# IO_Shield_With_Power_Supply_PCB.net
KiCad netlist of a schematic drawn in EAGLE
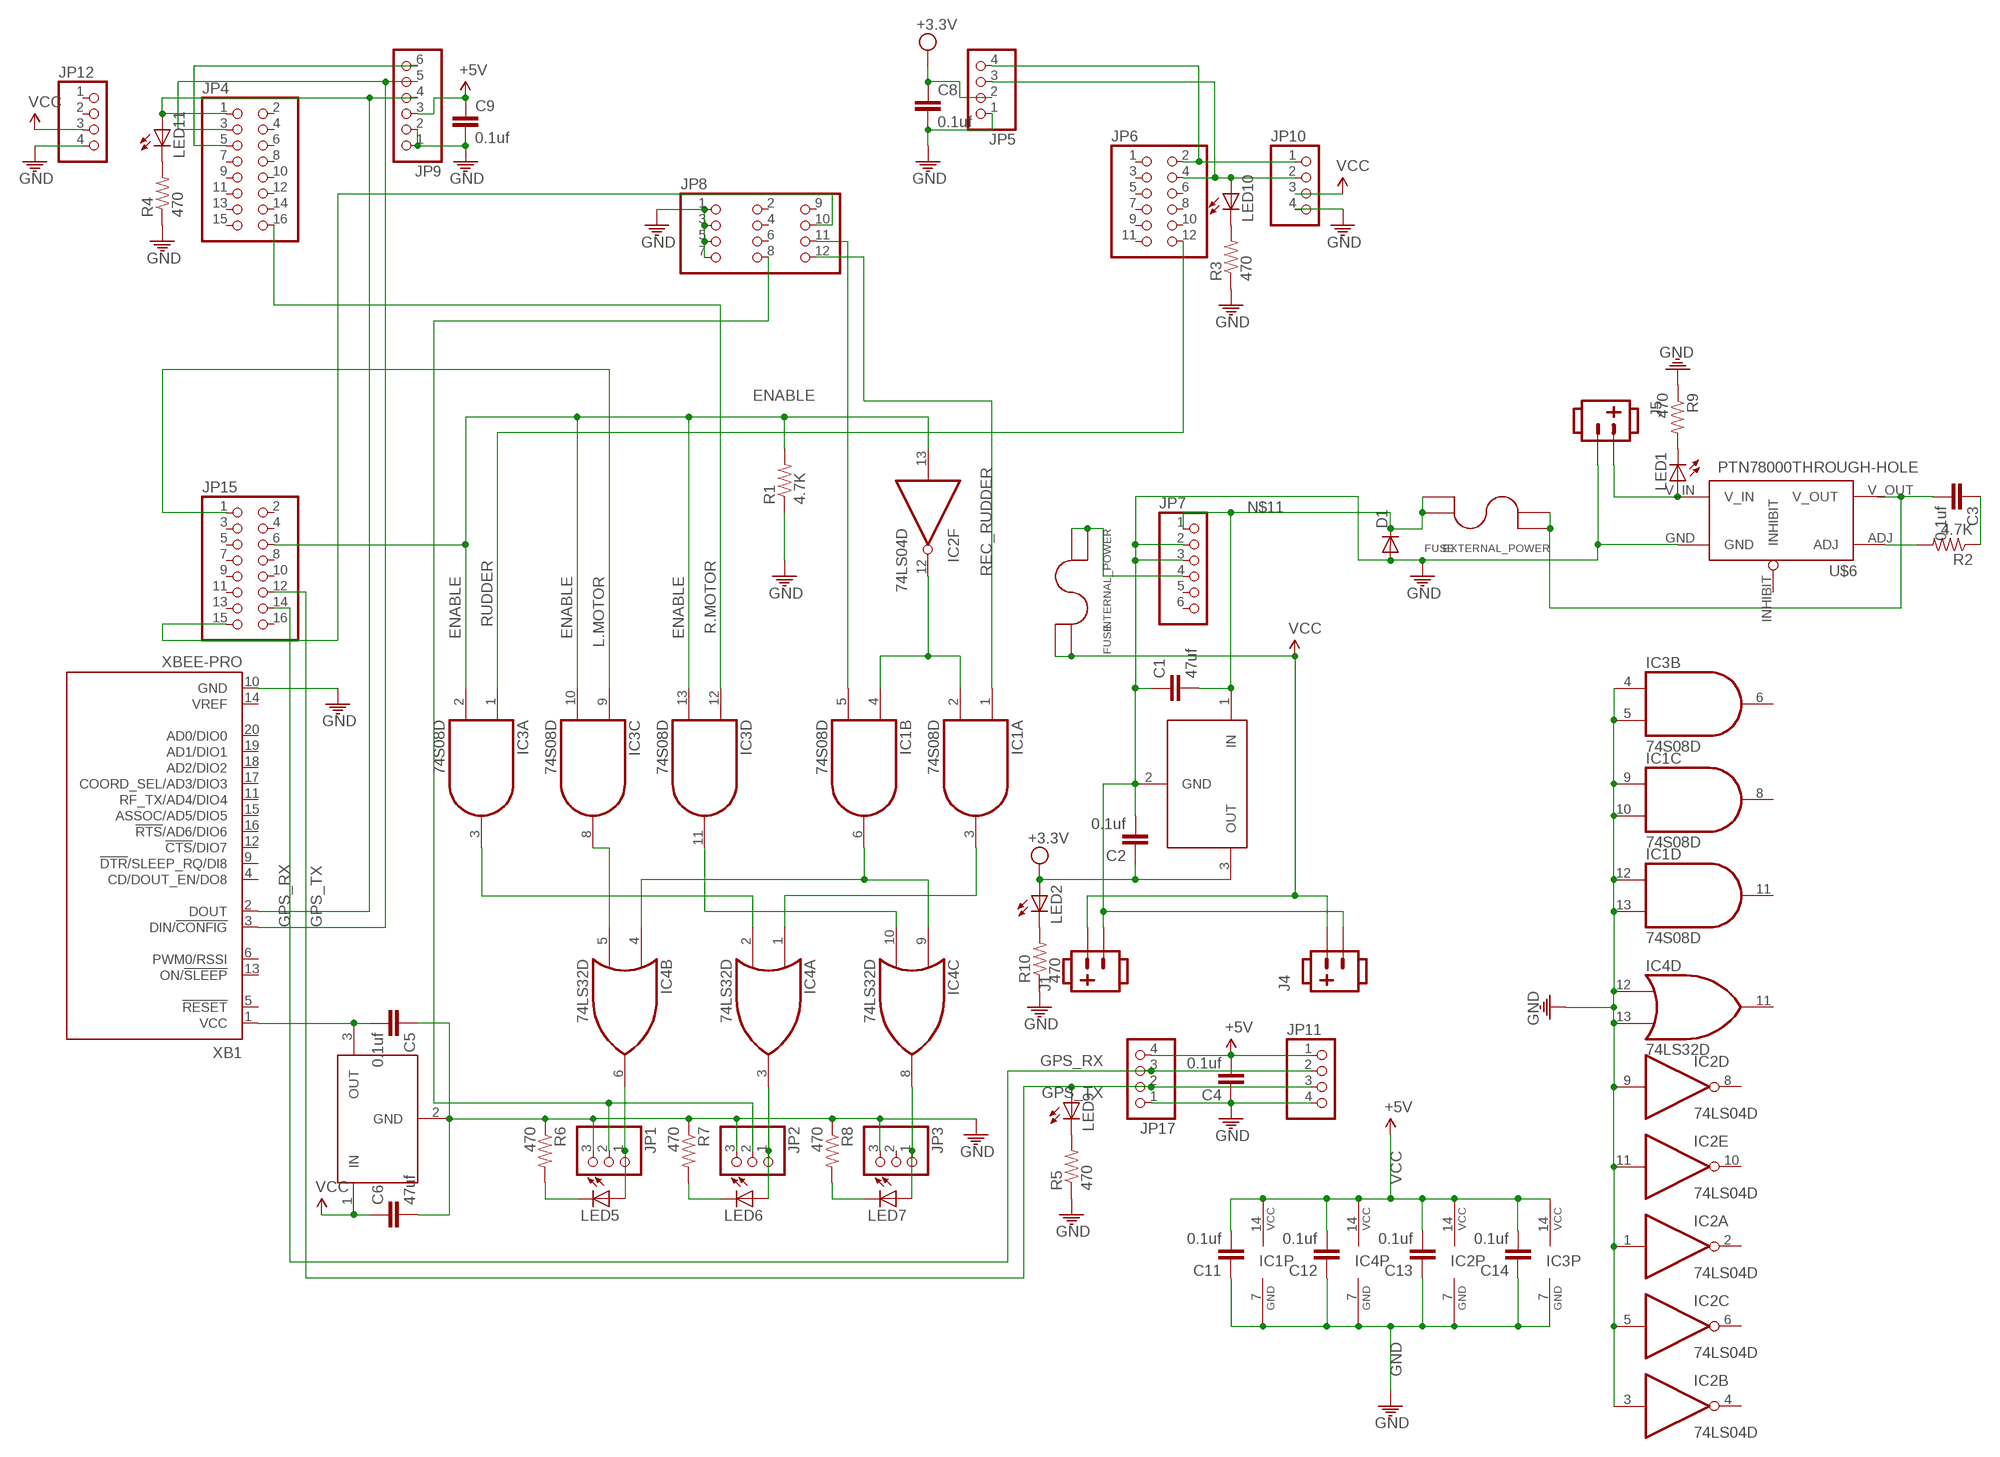
[diagram p0: schematic, sheet 1]

(export (version "E")
  (design (tool "Eeschema 10.0.6"))
  (components
    (comp (ref "C1")
      (value "47uf")
      (footprint "eagle-import:C0805")
      (libsource (lib "eagle-import") (part "C-EUC0805"))
    )
    (comp (ref "C2")
      (value "0.1uf")
      (footprint "eagle-import:C0805")
      (libsource (lib "eagle-import") (part "C-EUC0805"))
    )
    (comp (ref "C3")
      (value "0.1uf")
      (footprint "eagle-import:C0805")
      (libsource (lib "eagle-import") (part "C-EUC0805"))
    )
    (comp (ref "C4")
      (value "0.1uf")
      (footprint "eagle-import:C0805")
      (libsource (lib "eagle-import") (part "C-EUC0805"))
    )
    (comp (ref "C5")
      (value "0.1uf")
      (footprint "eagle-import:C0805")
      (libsource (lib "eagle-import") (part "C-EUC0805"))
    )
    (comp (ref "C6")
      (value "47uf")
      (footprint "eagle-import:C0805")
      (libsource (lib "eagle-import") (part "C-EUC0805"))
    )
    (comp (ref "C8")
      (value "0.1uf")
      (footprint "eagle-import:C0805")
      (libsource (lib "eagle-import") (part "C-EUC0805"))
    )
    (comp (ref "C9")
      (value "0.1uf")
      (footprint "eagle-import:C0805")
      (libsource (lib "eagle-import") (part "C-EUC0805"))
    )
    (comp (ref "C11")
      (value "0.1uf")
      (footprint "eagle-import:C0805")
      (libsource (lib "eagle-import") (part "C-EUC0805"))
    )
    (comp (ref "C12")
      (value "0.1uf")
      (footprint "eagle-import:C0805")
      (libsource (lib "eagle-import") (part "C-EUC0805"))
    )
    (comp (ref "C13")
      (value "0.1uf")
      (footprint "eagle-import:C0805")
      (libsource (lib "eagle-import") (part "C-EUC0805"))
    )
    (comp (ref "C14")
      (value "0.1uf")
      (footprint "eagle-import:C0805")
      (libsource (lib "eagle-import") (part "C-EUC0805"))
    )
    (comp (ref "D1")
      (value "DIODEPTH")
      (footprint "eagle-import:DIODE-1N4001")
      (libsource (lib "eagle-import") (part "DIODEPTH"))
    )
    (comp (ref "EXTERNAL_POWER")
      (value "FUSE")
      (footprint "eagle-import:FUSE_2AG")
      (libsource (lib "eagle-import") (part "FUSE"))
    )
    (comp (ref "IC1")
      (value "74S08D")
      (footprint "eagle-import:SO14")
      (libsource (lib "eagle-import") (part "7408DS"))
    )
    (comp (ref "IC2")
      (value "74LS04D")
      (footprint "eagle-import:SO14")
      (libsource (lib "eagle-import") (part "7404DLS"))
    )
    (comp (ref "IC3")
      (value "74S08D")
      (footprint "eagle-import:SO14")
      (libsource (lib "eagle-import") (part "7408DS"))
    )
    (comp (ref "IC4")
      (value "74LS32D")
      (footprint "eagle-import:SO14")
      (libsource (lib "eagle-import") (part "7432DLS"))
    )
    (comp (ref "INTERNAL_POWER")
      (value "FUSE")
      (footprint "eagle-import:FUSE_2AG")
      (libsource (lib "eagle-import") (part "FUSE"))
    )
    (comp (ref "J1")
      (value "POW_CONNECTFEMALE-RA")
      (footprint "eagle-import:SOCKET-FEMALE_RA-3.96MM-2")
      (libsource (lib "eagle-import") (part "POW_CONNECTFEMALE-RA"))
    )
    (comp (ref "J4")
      (value "POW_CONNECTFEMALE-RA")
      (footprint "eagle-import:SOCKET-FEMALE_RA-3.96MM-2")
      (libsource (lib "eagle-import") (part "POW_CONNECTFEMALE-RA"))
    )
    (comp (ref "J5")
      (value "POW_CONNECTFEMALE-RA")
      (footprint "eagle-import:SOCKET-FEMALE_RA-3.96MM-2")
      (libsource (lib "eagle-import") (part "POW_CONNECTFEMALE-RA"))
    )
    (comp (ref "JP1")
      (value "PINHD-1X3/90")
      (footprint "eagle-import:1X03_90")
      (libsource (lib "eagle-import") (part "PINHD-1X3/90"))
    )
    (comp (ref "JP2")
      (value "PINHD-1X3/90")
      (footprint "eagle-import:1X03_90")
      (libsource (lib "eagle-import") (part "PINHD-1X3/90"))
    )
    (comp (ref "JP3")
      (value "PINHD-1X3/90")
      (footprint "eagle-import:1X03_90")
      (libsource (lib "eagle-import") (part "PINHD-1X3/90"))
    )
    (comp (ref "JP4")
      (value "PINHD-2X8")
      (footprint "eagle-import:2X08")
      (libsource (lib "eagle-import") (part "PINHD-2X8"))
    )
    (comp (ref "JP5")
      (value "PINHD-1X4")
      (footprint "eagle-import:1X04")
      (libsource (lib "eagle-import") (part "PINHD-1X4"))
    )
    (comp (ref "JP6")
      (value "PINHD-2X6")
      (footprint "eagle-import:2X06")
      (libsource (lib "eagle-import") (part "PINHD-2X6"))
    )
    (comp (ref "JP7")
      (value "PINHD-1X6")
      (footprint "eagle-import:1X06")
      (libsource (lib "eagle-import") (part "pinhead_PINHD-1X6"))
    )
    (comp (ref "JP8")
      (value "PINHD-2X4")
      (footprint "eagle-import:2X04")
      (libsource (lib "eagle-import") (part "PINHD-2X4"))
    )
    (comp (ref "JP9")
      (value "PINHD-1X6")
      (footprint "eagle-import:1X06")
      (libsource (lib "eagle-import") (part "PINHD-1X6"))
    )
    (comp (ref "JP10")
      (value "PINHD-1X4/90")
      (footprint "eagle-import:1X04_90")
      (libsource (lib "eagle-import") (part "pinhead_PINHD-1X4/90"))
    )
    (comp (ref "JP11")
      (value "PINHD-1X4/90")
      (footprint "eagle-import:1X04_90")
      (libsource (lib "eagle-import") (part "pinhead_PINHD-1X4/90"))
    )
    (comp (ref "JP12")
      (value "PINHD-1X4/90")
      (footprint "eagle-import:1X04_90")
      (libsource (lib "eagle-import") (part "pinhead_PINHD-1X4/90"))
    )
    (comp (ref "JP15")
      (value "PINHD-2X8")
      (footprint "eagle-import:2X08")
      (libsource (lib "eagle-import") (part "PINHD-2X8"))
    )
    (comp (ref "JP17")
      (value "PINHD-1X4")
      (footprint "eagle-import:1X04")
      (libsource (lib "eagle-import") (part "pinhead_PINHD-1X4"))
    )
    (comp (ref "LED1")
      (value "LED-FKIT-1206")
      (footprint "eagle-import:FKIT-LED-1206")
      (libsource (lib "eagle-import") (part "LED-FKIT-1206"))
    )
    (comp (ref "LED2")
      (value "LED-FKIT-1206")
      (footprint "eagle-import:FKIT-LED-1206")
      (libsource (lib "eagle-import") (part "LED-FKIT-1206"))
    )
    (comp (ref "LED5")
      (value "LED-FKIT-1206")
      (footprint "eagle-import:FKIT-LED-1206")
      (libsource (lib "eagle-import") (part "LED-FKIT-1206"))
    )
    (comp (ref "LED6")
      (value "LED-FKIT-1206")
      (footprint "eagle-import:FKIT-LED-1206")
      (libsource (lib "eagle-import") (part "LED-FKIT-1206"))
    )
    (comp (ref "LED7")
      (value "LED-FKIT-1206")
      (footprint "eagle-import:FKIT-LED-1206")
      (libsource (lib "eagle-import") (part "LED-FKIT-1206"))
    )
    (comp (ref "LED9")
      (value "LED-FKIT-1206")
      (footprint "eagle-import:FKIT-LED-1206")
      (libsource (lib "eagle-import") (part "LED-FKIT-1206"))
    )
    (comp (ref "LED10")
      (value "LED-FKIT-1206")
      (footprint "eagle-import:FKIT-LED-1206")
      (libsource (lib "eagle-import") (part "LED-FKIT-1206"))
    )
    (comp (ref "LED11")
      (value "LED-FKIT-1206")
      (footprint "eagle-import:FKIT-LED-1206")
      (libsource (lib "eagle-import") (part "LED-FKIT-1206"))
    )
    (comp (ref "R1")
      (value "4.7K")
      (footprint "eagle-import:0805")
      (libsource (lib "eagle-import") (part "RESISTOR0805-RES"))
    )
    (comp (ref "R2")
      (value "4.7K")
      (footprint "eagle-import:0805")
      (libsource (lib "eagle-import") (part "RESISTOR0805-RES"))
    )
    (comp (ref "R3")
      (value "470")
      (footprint "eagle-import:0805")
      (libsource (lib "eagle-import") (part "RESISTOR0805-RES"))
    )
    (comp (ref "R4")
      (value "470")
      (footprint "eagle-import:0805")
      (libsource (lib "eagle-import") (part "RESISTOR0805-RES"))
    )
    (comp (ref "R5")
      (value "470")
      (footprint "eagle-import:0805")
      (libsource (lib "eagle-import") (part "RESISTOR0805-RES"))
    )
    (comp (ref "R6")
      (value "470")
      (footprint "eagle-import:0805")
      (libsource (lib "eagle-import") (part "RESISTOR0805-RES"))
    )
    (comp (ref "R7")
      (value "470")
      (footprint "eagle-import:0805")
      (libsource (lib "eagle-import") (part "RESISTOR0805-RES"))
    )
    (comp (ref "R8")
      (value "470")
      (footprint "eagle-import:0805")
      (libsource (lib "eagle-import") (part "RESISTOR0805-RES"))
    )
    (comp (ref "R9")
      (value "470")
      (footprint "eagle-import:0805")
      (libsource (lib "eagle-import") (part "RESISTOR0805-RES"))
    )
    (comp (ref "R10")
      (value "470")
      (footprint "eagle-import:0805")
      (libsource (lib "eagle-import") (part "RESISTOR0805-RES"))
    )
    (comp (ref "U$1")
      (value "LM3940IMP-3.3")
      (footprint "eagle-import:SOT223")
      (libsource (lib "eagle-import") (part "LM3940IMP-3.3"))
    )
    (comp (ref "U$6")
      (value "PTN78000THROUGH-HOLE")
      (footprint "eagle-import:PTN78000")
      (libsource (lib "eagle-import") (part "PTN78000THROUGH-HOLE"))
    )
    (comp (ref "U$7")
      (value "LM3940IMP-3.3")
      (footprint "eagle-import:SOT223")
      (libsource (lib "eagle-import") (part "LM3940IMP-3.3"))
    )
    (comp (ref "XB1")
      (value "XBEE-PRO")
      (footprint "eagle-import:XBEE-PRO")
      (fields (field (name "MPN") "XBP24-AWI-001"))
      (libsource (lib "eagle-import") (part "XBEE-PRO"))
    )
  )
  (nets
    (net (code "1") (name "+3.3V") (class "Default")
      (node (ref "C2") (pin "1") (pinfunction "1_1") (pintype "passive"))
      (node (ref "C8") (pin "1") (pinfunction "1_1") (pintype "passive"))
      (node (ref "JP5") (pin "2") (pinfunction "2_2") (pintype "passive"))
      (node (ref "LED2") (pin "A") (pinfunction "A_A") (pintype "passive"))
      (node (ref "U$1") (pin "3") (pinfunction "OUT_3") (pintype "power_in"))
    )
    (net (code "2") (name "+5V") (class "Default")
      (node (ref "C11") (pin "2") (pinfunction "2_2") (pintype "passive"))
      (node (ref "C12") (pin "2") (pinfunction "2_2") (pintype "passive"))
      (node (ref "C13") (pin "2") (pinfunction "2_2") (pintype "passive"))
      (node (ref "C14") (pin "2") (pinfunction "2_2") (pintype "passive"))
      (node (ref "C4") (pin "2") (pinfunction "2_2") (pintype "passive"))
      (node (ref "C6") (pin "1") (pinfunction "1_1") (pintype "passive"))
      (node (ref "C9") (pin "1") (pinfunction "1_1") (pintype "passive"))
      (node (ref "IC1") (pin "14") (pinfunction "VCC_14") (pintype "power_in"))
      (node (ref "IC2") (pin "14") (pinfunction "VCC_14") (pintype "power_in"))
      (node (ref "IC3") (pin "14") (pinfunction "VCC_14") (pintype "power_in"))
      (node (ref "IC4") (pin "14") (pinfunction "VCC_14") (pintype "power_in"))
      (node (ref "INTERNAL_POWER") (pin "P$3") (pinfunction "3_P$3") (pintype "bidirectional"))
      (node (ref "INTERNAL_POWER") (pin "P$4") (pinfunction "4_P$4") (pintype "bidirectional"))
      (node (ref "J1") (pin "1") (pinfunction "1_1") (pintype "passive"))
      (node (ref "J4") (pin "1") (pinfunction "1_1") (pintype "passive"))
      (node (ref "JP10") (pin "3") (pinfunction "3_3") (pintype "passive"))
      (node (ref "JP11") (pin "1") (pinfunction "1_1") (pintype "passive"))
      (node (ref "JP12") (pin "3") (pinfunction "3_3") (pintype "passive"))
      (node (ref "JP17") (pin "4") (pinfunction "4_4") (pintype "passive"))
      (node (ref "JP9") (pin "3") (pinfunction "3_3") (pintype "passive"))
      (node (ref "U$7") (pin "1") (pinfunction "IN_1") (pintype "power_in"))
    )
    (net (code "3") (name "/ENABLE") (class "Default")
      (node (ref "IC2") (pin "13") (pinfunction "I_13") (pintype "input"))
      (node (ref "IC3") (pin "10") (pinfunction "I1_10") (pintype "input"))
      (node (ref "IC3") (pin "13") (pinfunction "I1_13") (pintype "input"))
      (node (ref "IC3") (pin "2") (pinfunction "I1_2") (pintype "input"))
      (node (ref "JP15") (pin "6") (pinfunction "6_6") (pintype "passive"))
      (node (ref "R1") (pin "2") (pinfunction "2_2") (pintype "passive"))
    )
    (net (code "4") (name "/GPS_RX") (class "Default")
      (node (ref "JP11") (pin "2") (pinfunction "2_2") (pintype "passive"))
      (node (ref "JP15") (pin "14") (pinfunction "14_14") (pintype "passive"))
      (node (ref "JP17") (pin "3") (pinfunction "3_3") (pintype "passive"))
    )
    (net (code "5") (name "/GPS_TX") (class "Default")
      (node (ref "JP11") (pin "3") (pinfunction "3_3") (pintype "passive"))
      (node (ref "JP15") (pin "12") (pinfunction "12_12") (pintype "passive"))
      (node (ref "JP17") (pin "2") (pinfunction "2_2") (pintype "passive"))
      (node (ref "LED9") (pin "A") (pinfunction "A_A") (pintype "passive"))
    )
    (net (code "6") (name "/L.MOTOR") (class "Default")
      (node (ref "IC3") (pin "9") (pinfunction "I0_9") (pintype "input"))
      (node (ref "JP15") (pin "1") (pinfunction "1_1") (pintype "passive"))
    )
    (net (code "7") (name "/N$11") (class "Default")
      (node (ref "C1") (pin "2") (pinfunction "2_2") (pintype "passive"))
      (node (ref "D1") (pin "C") (pinfunction "C_C") (pintype "passive"))
      (node (ref "EXTERNAL_POWER") (pin "P$3") (pinfunction "3_P$3") (pintype "bidirectional"))
      (node (ref "EXTERNAL_POWER") (pin "P$4") (pinfunction "4_P$4") (pintype "bidirectional"))
      (node (ref "JP7") (pin "1") (pinfunction "1_1") (pintype "passive"))
      (node (ref "U$1") (pin "1") (pinfunction "IN_1") (pintype "power_in"))
    )
    (net (code "8") (name "/R.MOTOR") (class "Default")
      (node (ref "IC3") (pin "12") (pinfunction "I0_12") (pintype "input"))
      (node (ref "JP4") (pin "16") (pinfunction "16_16") (pintype "passive"))
    )
    (net (code "9") (name "/REC_RUDDER") (class "Default")
      (node (ref "IC1") (pin "1") (pinfunction "I0_1") (pintype "input"))
      (node (ref "JP8") (pin "12") (pinfunction "12_12") (pintype "passive"))
    )
    (net (code "10") (name "/RUDDER") (class "Default")
      (node (ref "IC3") (pin "1") (pinfunction "I0_1") (pintype "input"))
      (node (ref "JP6") (pin "12") (pinfunction "12_12") (pintype "passive"))
    )
    (net (code "11") (name "GND") (class "Default")
      (node (ref "C1") (pin "1") (pinfunction "1_1") (pintype "passive"))
      (node (ref "C11") (pin "1") (pinfunction "1_1") (pintype "passive"))
      (node (ref "C12") (pin "1") (pinfunction "1_1") (pintype "passive"))
      (node (ref "C13") (pin "1") (pinfunction "1_1") (pintype "passive"))
      (node (ref "C14") (pin "1") (pinfunction "1_1") (pintype "passive"))
      (node (ref "C2") (pin "2") (pinfunction "2_2") (pintype "passive"))
      (node (ref "C4") (pin "1") (pinfunction "1_1") (pintype "passive"))
      (node (ref "C5") (pin "1") (pinfunction "1_1") (pintype "passive"))
      (node (ref "C6") (pin "2") (pinfunction "2_2") (pintype "passive"))
      (node (ref "C8") (pin "2") (pinfunction "2_2") (pintype "passive"))
      (node (ref "C9") (pin "2") (pinfunction "2_2") (pintype "passive"))
      (node (ref "D1") (pin "A") (pinfunction "A_A") (pintype "passive"))
      (node (ref "IC1") (pin "10") (pinfunction "I1_10") (pintype "input"))
      (node (ref "IC1") (pin "12") (pinfunction "I0_12") (pintype "input"))
      (node (ref "IC1") (pin "13") (pinfunction "I1_13") (pintype "input"))
      (node (ref "IC1") (pin "7") (pinfunction "GND_7") (pintype "power_in"))
      (node (ref "IC1") (pin "9") (pinfunction "I0_9") (pintype "input"))
      (node (ref "IC2") (pin "1") (pinfunction "I_1") (pintype "input"))
      (node (ref "IC2") (pin "11") (pinfunction "I_11") (pintype "input"))
      (node (ref "IC2") (pin "3") (pinfunction "I_3") (pintype "input"))
      (node (ref "IC2") (pin "5") (pinfunction "I_5") (pintype "input"))
      (node (ref "IC2") (pin "7") (pinfunction "GND_7") (pintype "power_in"))
      (node (ref "IC2") (pin "9") (pinfunction "I_9") (pintype "input"))
      (node (ref "IC3") (pin "4") (pinfunction "I0_4") (pintype "input"))
      (node (ref "IC3") (pin "5") (pinfunction "I1_5") (pintype "input"))
      (node (ref "IC3") (pin "7") (pinfunction "GND_7") (pintype "power_in"))
      (node (ref "IC4") (pin "12") (pinfunction "I0_12") (pintype "input"))
      (node (ref "IC4") (pin "13") (pinfunction "I1_13") (pintype "input"))
      (node (ref "IC4") (pin "7") (pinfunction "GND_7") (pintype "power_in"))
      (node (ref "J1") (pin "2") (pinfunction "2_2") (pintype "passive"))
      (node (ref "J4") (pin "2") (pinfunction "2_2") (pintype "passive"))
      (node (ref "J5") (pin "2") (pinfunction "2_2") (pintype "passive"))
      (node (ref "JP1") (pin "3") (pinfunction "3_3") (pintype "passive"))
      (node (ref "JP10") (pin "4") (pinfunction "4_4") (pintype "passive"))
      (node (ref "JP11") (pin "4") (pinfunction "4_4") (pintype "passive"))
      (node (ref "JP12") (pin "4") (pinfunction "4_4") (pintype "passive"))
      (node (ref "JP17") (pin "1") (pinfunction "1_1") (pintype "passive"))
      (node (ref "JP2") (pin "3") (pinfunction "3_3") (pintype "passive"))
      (node (ref "JP3") (pin "3") (pinfunction "3_3") (pintype "passive"))
      (node (ref "JP5") (pin "1") (pinfunction "1_1") (pintype "passive"))
      (node (ref "JP7") (pin "2") (pinfunction "2_2") (pintype "passive"))
      (node (ref "JP7") (pin "3") (pinfunction "3_3") (pintype "passive"))
      (node (ref "JP8") (pin "1") (pinfunction "1_1") (pintype "passive"))
      (node (ref "JP8") (pin "3") (pinfunction "3_3") (pintype "passive"))
      (node (ref "JP8") (pin "5") (pinfunction "5_5") (pintype "passive"))
      (node (ref "JP8") (pin "7") (pinfunction "7_7") (pintype "passive"))
      (node (ref "JP9") (pin "1") (pinfunction "1_1") (pintype "passive"))
      (node (ref "JP9") (pin "2") (pinfunction "2_2") (pintype "passive"))
      (node (ref "R1") (pin "1") (pinfunction "1_1") (pintype "passive"))
      (node (ref "R10") (pin "1") (pinfunction "1_1") (pintype "passive"))
      (node (ref "R3") (pin "1") (pinfunction "1_1") (pintype "passive"))
      (node (ref "R4") (pin "1") (pinfunction "1_1") (pintype "passive"))
      (node (ref "R5") (pin "1") (pinfunction "1_1") (pintype "passive"))
      (node (ref "R6") (pin "1") (pinfunction "1_1") (pintype "passive"))
      (node (ref "R7") (pin "1") (pinfunction "1_1") (pintype "passive"))
      (node (ref "R8") (pin "1") (pinfunction "1_1") (pintype "passive"))
      (node (ref "R9") (pin "1") (pinfunction "1_1") (pintype "passive"))
      (node (ref "U$1") (pin "2") (pinfunction "GND_2") (pintype "power_in"))
      (node (ref "U$6") (pin "GND") (pinfunction "GND_GND") (pintype "power_in"))
      (node (ref "U$7") (pin "2") (pinfunction "GND_2") (pintype "power_in"))
      (node (ref "XB1") (pin "10") (pinfunction "GND_10") (pintype "power_in"))
    )
    (net (code "12") (name "Net-(C3-Pad1)") (class "Default")
      (node (ref "C3") (pin "1") (pinfunction "1_1") (pintype "passive"))
      (node (ref "R2") (pin "1") (pinfunction "1_1") (pintype "passive"))
    )
    (net (code "13") (name "Net-(EXTERNAL_POWER-1)") (class "Default")
      (node (ref "C3") (pin "2") (pinfunction "2_2") (pintype "passive"))
      (node (ref "EXTERNAL_POWER") (pin "P$1") (pinfunction "1_P$1") (pintype "bidirectional"))
      (node (ref "EXTERNAL_POWER") (pin "P$2") (pinfunction "2_P$2") (pintype "bidirectional"))
      (node (ref "U$6") (pin "V_OUT") (pinfunction "V_OUT_V_OUT") (pintype "output"))
    )
    (net (code "14") (name "Net-(IC1A-I1)") (class "Default")
      (node (ref "IC1") (pin "2") (pinfunction "I1_2") (pintype "input"))
      (node (ref "IC1") (pin "4") (pinfunction "I0_4") (pintype "input"))
      (node (ref "IC2") (pin "12") (pinfunction "O_12") (pintype "output"))
    )
    (net (code "15") (name "Net-(IC1A-O)") (class "Default")
      (node (ref "IC1") (pin "3") (pinfunction "O_3") (pintype "output"))
      (node (ref "IC4") (pin "1") (pinfunction "I0_1") (pintype "input"))
    )
    (net (code "16") (name "Net-(IC1B-I1)") (class "Default")
      (node (ref "IC1") (pin "5") (pinfunction "I1_5") (pintype "input"))
      (node (ref "JP8") (pin "11") (pinfunction "11_11") (pintype "passive"))
    )
    (net (code "17") (name "Net-(IC1B-O)") (class "Default")
      (node (ref "IC1") (pin "6") (pinfunction "O_6") (pintype "output"))
      (node (ref "IC4") (pin "4") (pinfunction "I0_4") (pintype "input"))
      (node (ref "IC4") (pin "9") (pinfunction "I0_9") (pintype "input"))
    )
    (net (code "18") (name "Net-(IC3A-O)") (class "Default")
      (node (ref "IC3") (pin "3") (pinfunction "O_3") (pintype "output"))
      (node (ref "IC4") (pin "2") (pinfunction "I1_2") (pintype "input"))
    )
    (net (code "19") (name "Net-(IC3C-O)") (class "Default")
      (node (ref "IC3") (pin "8") (pinfunction "O_8") (pintype "output"))
      (node (ref "IC4") (pin "5") (pinfunction "I1_5") (pintype "input"))
    )
    (net (code "20") (name "Net-(IC3D-O)") (class "Default")
      (node (ref "IC3") (pin "11") (pinfunction "O_11") (pintype "output"))
      (node (ref "IC4") (pin "10") (pinfunction "I1_10") (pintype "input"))
    )
    (net (code "21") (name "Net-(IC4A-O)") (class "Default")
      (node (ref "IC4") (pin "3") (pinfunction "O_3") (pintype "output"))
      (node (ref "JP2") (pin "1") (pinfunction "1_1") (pintype "passive"))
      (node (ref "LED6") (pin "A") (pinfunction "A_A") (pintype "passive"))
    )
    (net (code "22") (name "Net-(IC4B-O)") (class "Default")
      (node (ref "IC4") (pin "6") (pinfunction "O_6") (pintype "output"))
      (node (ref "JP1") (pin "1") (pinfunction "1_1") (pintype "passive"))
      (node (ref "LED5") (pin "A") (pinfunction "A_A") (pintype "passive"))
    )
    (net (code "23") (name "Net-(IC4C-O)") (class "Default")
      (node (ref "IC4") (pin "8") (pinfunction "O_8") (pintype "output"))
      (node (ref "JP3") (pin "1") (pinfunction "1_1") (pintype "passive"))
      (node (ref "LED7") (pin "A") (pinfunction "A_A") (pintype "passive"))
    )
    (net (code "24") (name "Net-(INTERNAL_POWER-1)") (class "Default")
      (node (ref "INTERNAL_POWER") (pin "P$1") (pinfunction "1_P$1") (pintype "bidirectional"))
      (node (ref "INTERNAL_POWER") (pin "P$2") (pinfunction "2_P$2") (pintype "bidirectional"))
      (node (ref "JP7") (pin "4") (pinfunction "4_4") (pintype "passive"))
    )
    (net (code "25") (name "Net-(J5-Pad1)") (class "Default")
      (node (ref "J5") (pin "1") (pinfunction "1_1") (pintype "passive"))
      (node (ref "LED1") (pin "A") (pinfunction "A_A") (pintype "passive"))
      (node (ref "U$6") (pin "V_IN") (pinfunction "V_IN_V_IN") (pintype "power_in"))
    )
    (net (code "26") (name "Net-(JP1-Pad2)") (class "Default")
      (node (ref "JP1") (pin "2") (pinfunction "2_2") (pintype "passive"))
      (node (ref "JP2") (pin "2") (pinfunction "2_2") (pintype "passive"))
      (node (ref "JP8") (pin "8") (pinfunction "8_8") (pintype "passive"))
    )
    (net (code "27") (name "Net-(JP4-Pad5)") (class "Default")
      (node (ref "JP4") (pin "5") (pinfunction "5_5") (pintype "passive"))
      (node (ref "JP9") (pin "6") (pinfunction "6_6") (pintype "passive"))
    )
    (net (code "28") (name "Net-(JP8-9)") (class "Default")
      (node (ref "JP15") (pin "15") (pinfunction "15_15") (pintype "passive"))
      (node (ref "JP8") (pin "10") (pinfunction "9_10") (pintype "passive"))
    )
    (net (code "29") (name "Net-(JP10-Pad1)") (class "Default")
      (node (ref "JP10") (pin "1") (pinfunction "1_1") (pintype "passive"))
      (node (ref "JP5") (pin "4") (pinfunction "4_4") (pintype "passive"))
      (node (ref "JP6") (pin "2") (pinfunction "2_2") (pintype "passive"))
    )
    (net (code "30") (name "Net-(JP10-Pad2)") (class "Default")
      (node (ref "JP10") (pin "2") (pinfunction "2_2") (pintype "passive"))
      (node (ref "JP5") (pin "3") (pinfunction "3_3") (pintype "passive"))
      (node (ref "JP6") (pin "4") (pinfunction "4_4") (pintype "passive"))
      (node (ref "LED10") (pin "A") (pinfunction "A_A") (pintype "passive"))
    )
    (net (code "31") (name "Net-(LED1-PadC)") (class "Default")
      (node (ref "LED1") (pin "C") (pinfunction "C_C") (pintype "passive"))
      (node (ref "R9") (pin "2") (pinfunction "2_2") (pintype "passive"))
    )
    (net (code "32") (name "Net-(LED2-PadC)") (class "Default")
      (node (ref "LED2") (pin "C") (pinfunction "C_C") (pintype "passive"))
      (node (ref "R10") (pin "2") (pinfunction "2_2") (pintype "passive"))
    )
    (net (code "33") (name "Net-(LED5-PadC)") (class "Default")
      (node (ref "LED5") (pin "C") (pinfunction "C_C") (pintype "passive"))
      (node (ref "R6") (pin "2") (pinfunction "2_2") (pintype "passive"))
    )
    (net (code "34") (name "Net-(LED6-PadC)") (class "Default")
      (node (ref "LED6") (pin "C") (pinfunction "C_C") (pintype "passive"))
      (node (ref "R7") (pin "2") (pinfunction "2_2") (pintype "passive"))
    )
    (net (code "35") (name "Net-(LED7-PadC)") (class "Default")
      (node (ref "LED7") (pin "C") (pinfunction "C_C") (pintype "passive"))
      (node (ref "R8") (pin "2") (pinfunction "2_2") (pintype "passive"))
    )
    (net (code "36") (name "Net-(LED9-PadC)") (class "Default")
      (node (ref "LED9") (pin "C") (pinfunction "C_C") (pintype "passive"))
      (node (ref "R5") (pin "2") (pinfunction "2_2") (pintype "passive"))
    )
    (net (code "37") (name "Net-(LED10-PadC)") (class "Default")
      (node (ref "LED10") (pin "C") (pinfunction "C_C") (pintype "passive"))
      (node (ref "R3") (pin "2") (pinfunction "2_2") (pintype "passive"))
    )
    (net (code "38") (name "Net-(LED11-PadC)") (class "Default")
      (node (ref "LED11") (pin "C") (pinfunction "C_C") (pintype "passive"))
      (node (ref "R4") (pin "2") (pinfunction "2_2") (pintype "passive"))
    )
    (net (code "39") (name "Net-(R2-Pad2)") (class "Default")
      (node (ref "R2") (pin "2") (pinfunction "2_2") (pintype "passive"))
      (node (ref "U$6") (pin "ADJ") (pinfunction "ADJ_ADJ") (pintype "input"))
    )
    (net (code "40") (name "Net-(U$7-OUT)") (class "Default")
      (node (ref "C5") (pin "2") (pinfunction "2_2") (pintype "passive"))
      (node (ref "U$7") (pin "3") (pinfunction "OUT_3") (pintype "power_in"))
      (node (ref "XB1") (pin "1") (pinfunction "VCC_1") (pintype "power_in"))
    )
    (net (code "41") (name "Net-(XB1-DIN{slash}~{CONFIG})") (class "Default")
      (node (ref "JP4") (pin "3") (pinfunction "3_3") (pintype "passive"))
      (node (ref "JP9") (pin "5") (pinfunction "5_5") (pintype "passive"))
      (node (ref "XB1") (pin "3") (pinfunction "DIN/~{CONFIG}_3") (pintype "input"))
    )
    (net (code "42") (name "Net-(XB1-DOUT)") (class "Default")
      (node (ref "JP4") (pin "1") (pinfunction "1_1") (pintype "passive"))
      (node (ref "JP9") (pin "4") (pinfunction "4_4") (pintype "passive"))
      (node (ref "LED11") (pin "A") (pinfunction "A_A") (pintype "passive"))
      (node (ref "XB1") (pin "2") (pinfunction "DOUT_2") (pintype "output"))
    )
    (net (code "43") (name "unconnected-(IC1C-O-Pad8)") (class "Default")
      (node (ref "IC1") (pin "8") (pinfunction "O_8") (pintype "output"))
    )
    (net (code "44") (name "unconnected-(IC1D-O-Pad11)") (class "Default")
      (node (ref "IC1") (pin "11") (pinfunction "O_11") (pintype "output"))
    )
    (net (code "45") (name "unconnected-(IC2A-O-Pad2)") (class "Default")
      (node (ref "IC2") (pin "2") (pinfunction "O_2") (pintype "output"))
    )
    (net (code "46") (name "unconnected-(IC2B-O-Pad4)") (class "Default")
      (node (ref "IC2") (pin "4") (pinfunction "O_4") (pintype "output"))
    )
    (net (code "47") (name "unconnected-(IC2C-O-Pad6)") (class "Default")
      (node (ref "IC2") (pin "6") (pinfunction "O_6") (pintype "output"))
    )
    (net (code "48") (name "unconnected-(IC2D-O-Pad8)") (class "Default")
      (node (ref "IC2") (pin "8") (pinfunction "O_8") (pintype "output"))
    )
    (net (code "49") (name "unconnected-(IC2E-O-Pad10)") (class "Default")
      (node (ref "IC2") (pin "10") (pinfunction "O_10") (pintype "output"))
    )
    (net (code "50") (name "unconnected-(IC3B-O-Pad6)") (class "Default")
      (node (ref "IC3") (pin "6") (pinfunction "O_6") (pintype "output"))
    )
    (net (code "51") (name "unconnected-(IC4D-O-Pad11)") (class "Default")
      (node (ref "IC4") (pin "11") (pinfunction "O_11") (pintype "output"))
    )
    (net (code "52") (name "unconnected-(JP3-Pad2)") (class "Default")
      (node (ref "JP3") (pin "2") (pinfunction "2_2") (pintype "passive"))
    )
    (net (code "53") (name "unconnected-(JP4-Pad2)") (class "Default")
      (node (ref "JP4") (pin "2") (pinfunction "2_2") (pintype "passive"))
    )
    (net (code "54") (name "unconnected-(JP4-Pad4)") (class "Default")
      (node (ref "JP4") (pin "4") (pinfunction "4_4") (pintype "passive"))
    )
    (net (code "55") (name "unconnected-(JP4-Pad6)") (class "Default")
      (node (ref "JP4") (pin "6") (pinfunction "6_6") (pintype "passive"))
    )
    (net (code "56") (name "unconnected-(JP4-Pad7)") (class "Default")
      (node (ref "JP4") (pin "7") (pinfunction "7_7") (pintype "passive"))
    )
    (net (code "57") (name "unconnected-(JP4-Pad8)") (class "Default")
      (node (ref "JP4") (pin "8") (pinfunction "8_8") (pintype "passive"))
    )
    (net (code "58") (name "unconnected-(JP4-Pad9)") (class "Default")
      (node (ref "JP4") (pin "9") (pinfunction "9_9") (pintype "passive"))
    )
    (net (code "59") (name "unconnected-(JP4-Pad10)") (class "Default")
      (node (ref "JP4") (pin "10") (pinfunction "10_10") (pintype "passive"))
    )
    (net (code "60") (name "unconnected-(JP4-Pad11)") (class "Default")
      (node (ref "JP4") (pin "11") (pinfunction "11_11") (pintype "passive"))
    )
    (net (code "61") (name "unconnected-(JP4-Pad12)") (class "Default")
      (node (ref "JP4") (pin "12") (pinfunction "12_12") (pintype "passive"))
    )
    (net (code "62") (name "unconnected-(JP4-Pad13)") (class "Default")
      (node (ref "JP4") (pin "13") (pinfunction "13_13") (pintype "passive"))
    )
    (net (code "63") (name "unconnected-(JP4-Pad14)") (class "Default")
      (node (ref "JP4") (pin "14") (pinfunction "14_14") (pintype "passive"))
    )
    (net (code "64") (name "unconnected-(JP4-Pad15)") (class "Default")
      (node (ref "JP4") (pin "15") (pinfunction "15_15") (pintype "passive"))
    )
    (net (code "65") (name "unconnected-(JP6-Pad1)") (class "Default")
      (node (ref "JP6") (pin "1") (pinfunction "1_1") (pintype "passive"))
    )
    (net (code "66") (name "unconnected-(JP6-Pad3)") (class "Default")
      (node (ref "JP6") (pin "3") (pinfunction "3_3") (pintype "passive"))
    )
    (net (code "67") (name "unconnected-(JP6-Pad5)") (class "Default")
      (node (ref "JP6") (pin "5") (pinfunction "5_5") (pintype "passive"))
    )
    (net (code "68") (name "unconnected-(JP6-Pad6)") (class "Default")
      (node (ref "JP6") (pin "6") (pinfunction "6_6") (pintype "passive"))
    )
    (net (code "69") (name "unconnected-(JP6-Pad7)") (class "Default")
      (node (ref "JP6") (pin "7") (pinfunction "7_7") (pintype "passive"))
    )
    (net (code "70") (name "unconnected-(JP6-Pad8)") (class "Default")
      (node (ref "JP6") (pin "8") (pinfunction "8_8") (pintype "passive"))
    )
    (net (code "71") (name "unconnected-(JP6-Pad9)") (class "Default")
      (node (ref "JP6") (pin "9") (pinfunction "9_9") (pintype "passive"))
    )
    (net (code "72") (name "unconnected-(JP6-Pad10)") (class "Default")
      (node (ref "JP6") (pin "10") (pinfunction "10_10") (pintype "passive"))
    )
    (net (code "73") (name "unconnected-(JP6-Pad11)") (class "Default")
      (node (ref "JP6") (pin "11") (pinfunction "11_11") (pintype "passive"))
    )
    (net (code "74") (name "unconnected-(JP7-Pad5)") (class "Default")
      (node (ref "JP7") (pin "5") (pinfunction "5_5") (pintype "passive"))
    )
    (net (code "75") (name "unconnected-(JP7-Pad6)") (class "Default")
      (node (ref "JP7") (pin "6") (pinfunction "6_6") (pintype "passive"))
    )
    (net (code "76") (name "unconnected-(JP8-10-Pad9)") (class "Default")
      (node (ref "JP8") (pin "9") (pinfunction "10_9") (pintype "passive"))
    )
    (net (code "77") (name "unconnected-(JP8-Pad2)") (class "Default")
      (node (ref "JP8") (pin "2") (pinfunction "2_2") (pintype "passive"))
    )
    (net (code "78") (name "unconnected-(JP8-Pad4)") (class "Default")
      (node (ref "JP8") (pin "4") (pinfunction "4_4") (pintype "passive"))
    )
    (net (code "79") (name "unconnected-(JP8-Pad6)") (class "Default")
      (node (ref "JP8") (pin "6") (pinfunction "6_6") (pintype "passive"))
    )
    (net (code "80") (name "unconnected-(JP12-Pad1)") (class "Default")
      (node (ref "JP12") (pin "1") (pinfunction "1_1") (pintype "passive"))
    )
    (net (code "81") (name "unconnected-(JP12-Pad2)") (class "Default")
      (node (ref "JP12") (pin "2") (pinfunction "2_2") (pintype "passive"))
    )
    (net (code "82") (name "unconnected-(JP15-Pad2)") (class "Default")
      (node (ref "JP15") (pin "2") (pinfunction "2_2") (pintype "passive"))
    )
    (net (code "83") (name "unconnected-(JP15-Pad3)") (class "Default")
      (node (ref "JP15") (pin "3") (pinfunction "3_3") (pintype "passive"))
    )
    (net (code "84") (name "unconnected-(JP15-Pad4)") (class "Default")
      (node (ref "JP15") (pin "4") (pinfunction "4_4") (pintype "passive"))
    )
    (net (code "85") (name "unconnected-(JP15-Pad5)") (class "Default")
      (node (ref "JP15") (pin "5") (pinfunction "5_5") (pintype "passive"))
    )
    (net (code "86") (name "unconnected-(JP15-Pad7)") (class "Default")
      (node (ref "JP15") (pin "7") (pinfunction "7_7") (pintype "passive"))
    )
    (net (code "87") (name "unconnected-(JP15-Pad8)") (class "Default")
      (node (ref "JP15") (pin "8") (pinfunction "8_8") (pintype "passive"))
    )
    (net (code "88") (name "unconnected-(JP15-Pad9)") (class "Default")
      (node (ref "JP15") (pin "9") (pinfunction "9_9") (pintype "passive"))
    )
    (net (code "89") (name "unconnected-(JP15-Pad10)") (class "Default")
      (node (ref "JP15") (pin "10") (pinfunction "10_10") (pintype "passive"))
    )
    (net (code "90") (name "unconnected-(JP15-Pad11)") (class "Default")
      (node (ref "JP15") (pin "11") (pinfunction "11_11") (pintype "passive"))
    )
    (net (code "91") (name "unconnected-(JP15-Pad13)") (class "Default")
      (node (ref "JP15") (pin "13") (pinfunction "13_13") (pintype "passive"))
    )
    (net (code "92") (name "unconnected-(JP15-Pad16)") (class "Default")
      (node (ref "JP15") (pin "16") (pinfunction "16_16") (pintype "passive"))
    )
    (net (code "93") (name "unconnected-(U$6-PadINHIBIT)") (class "Default")
      (node (ref "U$6") (pin "INHIBIT") (pinfunction "INHIBIT_INHIBIT") (pintype "input"))
    )
    (net (code "94") (name "unconnected-(XB1-AD0{slash}DIO0-Pad20)") (class "Default")
      (node (ref "XB1") (pin "20") (pinfunction "AD0/DIO0_20") (pintype "bidirectional"))
    )
    (net (code "95") (name "unconnected-(XB1-AD1{slash}DIO1-Pad19)") (class "Default")
      (node (ref "XB1") (pin "19") (pinfunction "AD1/DIO1_19") (pintype "bidirectional"))
    )
    (net (code "96") (name "unconnected-(XB1-AD2{slash}DIO2-Pad18)") (class "Default")
      (node (ref "XB1") (pin "18") (pinfunction "AD2/DIO2_18") (pintype "bidirectional"))
    )
    (net (code "97") (name "unconnected-(XB1-ASSOC{slash}AD5{slash}DIO5-Pad15)") (class "Default")
      (node (ref "XB1") (pin "15") (pinfunction "ASSOC/AD5/DIO5_15") (pintype "bidirectional"))
    )
    (net (code "98") (name "unconnected-(XB1-CD{slash}DOUT_EN{slash}DO8-Pad4)") (class "Default")
      (node (ref "XB1") (pin "4") (pinfunction "CD/DOUT_EN/DO8_4") (pintype "output"))
    )
    (net (code "99") (name "unconnected-(XB1-COORD_SEL{slash}AD3{slash}DIO3-Pad17)") (class "Default")
      (node (ref "XB1") (pin "17") (pinfunction "COORD_SEL/AD3/DIO3_17") (pintype "bidirectional"))
    )
    (net (code "100") (name "unconnected-(XB1-ON{slash}~{SLEEP}-Pad13)") (class "Default")
      (node (ref "XB1") (pin "13") (pinfunction "ON/~{SLEEP}_13") (pintype "output"))
    )
    (net (code "101") (name "unconnected-(XB1-PWM0{slash}RSSI-Pad6)") (class "Default")
      (node (ref "XB1") (pin "6") (pinfunction "PWM0/RSSI_6") (pintype "output"))
    )
    (net (code "102") (name "unconnected-(XB1-RF_TX{slash}AD4{slash}DIO4-Pad11)") (class "Default")
      (node (ref "XB1") (pin "11") (pinfunction "RF_TX/AD4/DIO4_11") (pintype "bidirectional"))
    )
    (net (code "103") (name "unconnected-(XB1-VREF-Pad14)") (class "Default")
      (node (ref "XB1") (pin "14") (pinfunction "VREF_14") (pintype "input"))
    )
    (net (code "104") (name "unconnected-(XB1-~{CTS}{slash}DIO7-Pad12)") (class "Default")
      (node (ref "XB1") (pin "12") (pinfunction "~{CTS}/DIO7_12") (pintype "bidirectional"))
    )
    (net (code "105") (name "unconnected-(XB1-~{DTR}{slash}SLEEP_RQ{slash}DI8-Pad9)") (class "Default")
      (node (ref "XB1") (pin "9") (pinfunction "~{DTR}/SLEEP_RQ/DI8_9") (pintype "bidirectional"))
    )
    (net (code "106") (name "unconnected-(XB1-~{RESET}-Pad5)") (class "Default")
      (node (ref "XB1") (pin "5") (pinfunction "~{RESET}_5") (pintype "input"))
    )
    (net (code "107") (name "unconnected-(XB1-~{RTS}{slash}AD6{slash}DIO6-Pad16)") (class "Default")
      (node (ref "XB1") (pin "16") (pinfunction "~{RTS}/AD6/DIO6_16") (pintype "bidirectional"))
    )
  )
)
